# AmbientLight-1.net
KiCad netlist of a schematic drawn in EAGLE
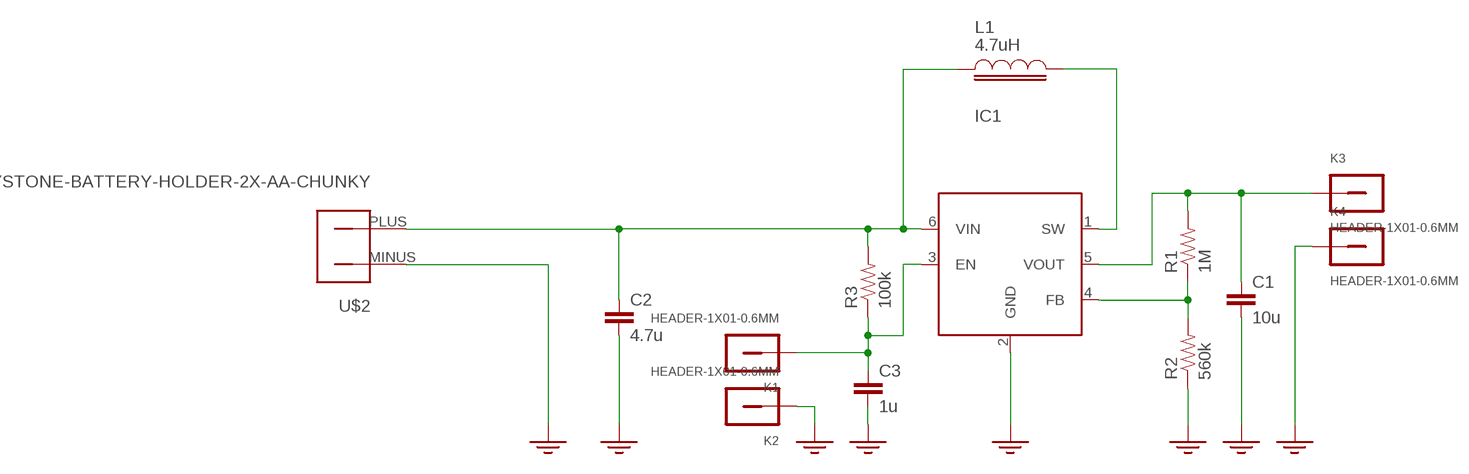
[diagram p0: schematic, sheet 1]

(export (version "E")
  (design (tool "Eeschema 10.0.6"))
  (components
    (comp (ref "C1")
      (value "10u")
      (footprint "eagle-import:0805-WIDE")
      (libsource (lib "eagle-import") (part "CAP-0805-WIDE"))
    )
    (comp (ref "C2")
      (value "4.7u")
      (footprint "eagle-import:0603-MIN")
      (libsource (lib "eagle-import") (part "CAP-0603-MIN"))
    )
    (comp (ref "C3")
      (value "1u")
      (footprint "eagle-import:0603-MIN")
      (libsource (lib "eagle-import") (part "CAP-0603-MIN"))
    )
    (comp (ref "IC1")
      (value "SWITCHING-REGULATOR-VARIABLE-BOOST-MCP1640")
      (footprint "eagle-import:SOT23-6")
      (libsource (lib "eagle-import") (part "SWITCHING-REGULATOR-VARIABLE-BOOST-MCP1640"))
    )
    (comp (ref "K1")
      (value "HEADER-1X01-0.6MM")
      (footprint "eagle-import:HEADER-1X01-0.6MM-DIAM")
      (libsource (lib "eagle-import") (part "HEADER-1X01-0.6MM"))
    )
    (comp (ref "K2")
      (value "HEADER-1X01-0.6MM")
      (footprint "eagle-import:HEADER-1X01-0.6MM-DIAM")
      (libsource (lib "eagle-import") (part "HEADER-1X01-0.6MM"))
    )
    (comp (ref "K3")
      (value "HEADER-1X01-0.6MM")
      (footprint "eagle-import:HEADER-1X01-0.6MM-DIAM")
      (libsource (lib "eagle-import") (part "HEADER-1X01-0.6MM"))
    )
    (comp (ref "K4")
      (value "HEADER-1X01-0.6MM")
      (footprint "eagle-import:HEADER-1X01-0.6MM-DIAM")
      (libsource (lib "eagle-import") (part "HEADER-1X01-0.6MM"))
    )
    (comp (ref "L1")
      (value "4.7uH")
      (footprint "eagle-import:1210-INDUCTOR-MIN")
      (libsource (lib "eagle-import") (part "INDUCTOR-1210-MIN"))
    )
    (comp (ref "R1")
      (value "1M")
      (footprint "eagle-import:0603-MIN")
      (libsource (lib "eagle-import") (part "RESISTOR-0603-MIN"))
    )
    (comp (ref "R2")
      (value "560k")
      (footprint "eagle-import:0603-MIN")
      (libsource (lib "eagle-import") (part "RESISTOR-0603-MIN"))
    )
    (comp (ref "R3")
      (value "100k")
      (footprint "eagle-import:0603-MIN")
      (libsource (lib "eagle-import") (part "RESISTOR-0603-MIN"))
    )
    (comp (ref "U$2")
      (value "KEYSTONE-BATTERY-HOLDER-2X-AA-CHUNKY")
      (footprint "eagle-import:KEYSTONE-BATTERY-HOLDER-2X-AA-CHUNKY")
      (libsource (lib "eagle-import") (part "KEYSTONE-BATTERY-HOLDER-2X-AA-CHUNKY"))
    )
  )
  (nets
    (net (code "1") (name "GND") (class "Default")
      (node (ref "C1") (pin "1") (pinfunction "1_1") (pintype "bidirectional"))
      (node (ref "C2") (pin "1") (pinfunction "1_1") (pintype "bidirectional"))
      (node (ref "C3") (pin "1") (pinfunction "1_1") (pintype "bidirectional"))
      (node (ref "IC1") (pin "2") (pinfunction "GND_2") (pintype "bidirectional"))
      (node (ref "K2") (pin "P$1") (pinfunction "P$1_P$1") (pintype "bidirectional"))
      (node (ref "K4") (pin "P$1") (pinfunction "P$1_P$1") (pintype "bidirectional"))
      (node (ref "R2") (pin "1") (pinfunction "1_1") (pintype "passive"))
      (node (ref "U$2") (pin "MINUS") (pinfunction "PLUS_MINUS") (pintype "power_in"))
    )
    (net (code "2") (name "Net-(IC1-EN)") (class "Default")
      (node (ref "C3") (pin "2") (pinfunction "2_2") (pintype "bidirectional"))
      (node (ref "IC1") (pin "3") (pinfunction "EN_3") (pintype "bidirectional"))
      (node (ref "K1") (pin "P$1") (pinfunction "P$1_P$1") (pintype "bidirectional"))
      (node (ref "R3") (pin "1") (pinfunction "1_1") (pintype "passive"))
    )
    (net (code "3") (name "Net-(IC1-FB)") (class "Default")
      (node (ref "IC1") (pin "4") (pinfunction "FB_4") (pintype "bidirectional"))
      (node (ref "R1") (pin "1") (pinfunction "1_1") (pintype "passive"))
      (node (ref "R2") (pin "2") (pinfunction "2_2") (pintype "passive"))
    )
    (net (code "4") (name "Net-(IC1-SW)") (class "Default")
      (node (ref "IC1") (pin "1") (pinfunction "SW_1") (pintype "bidirectional"))
      (node (ref "L1") (pin "2") (pinfunction "2_2") (pintype "bidirectional"))
    )
    (net (code "5") (name "Net-(IC1-VIN)") (class "Default")
      (node (ref "C2") (pin "2") (pinfunction "2_2") (pintype "bidirectional"))
      (node (ref "IC1") (pin "6") (pinfunction "VIN_6") (pintype "bidirectional"))
      (node (ref "L1") (pin "1") (pinfunction "1_1") (pintype "bidirectional"))
      (node (ref "R3") (pin "2") (pinfunction "2_2") (pintype "passive"))
      (node (ref "U$2") (pin "PLUS") (pinfunction "MINUS_PLUS") (pintype "power_in"))
    )
    (net (code "6") (name "Net-(IC1-VOUT)") (class "Default")
      (node (ref "C1") (pin "2") (pinfunction "2_2") (pintype "bidirectional"))
      (node (ref "IC1") (pin "5") (pinfunction "VOUT_5") (pintype "bidirectional"))
      (node (ref "K3") (pin "P$1") (pinfunction "P$1_P$1") (pintype "bidirectional"))
      (node (ref "R1") (pin "2") (pinfunction "2_2") (pintype "passive"))
    )
  )
)
